# 7seg-micro.net
KiCad netlist of a schematic drawn in EAGLE
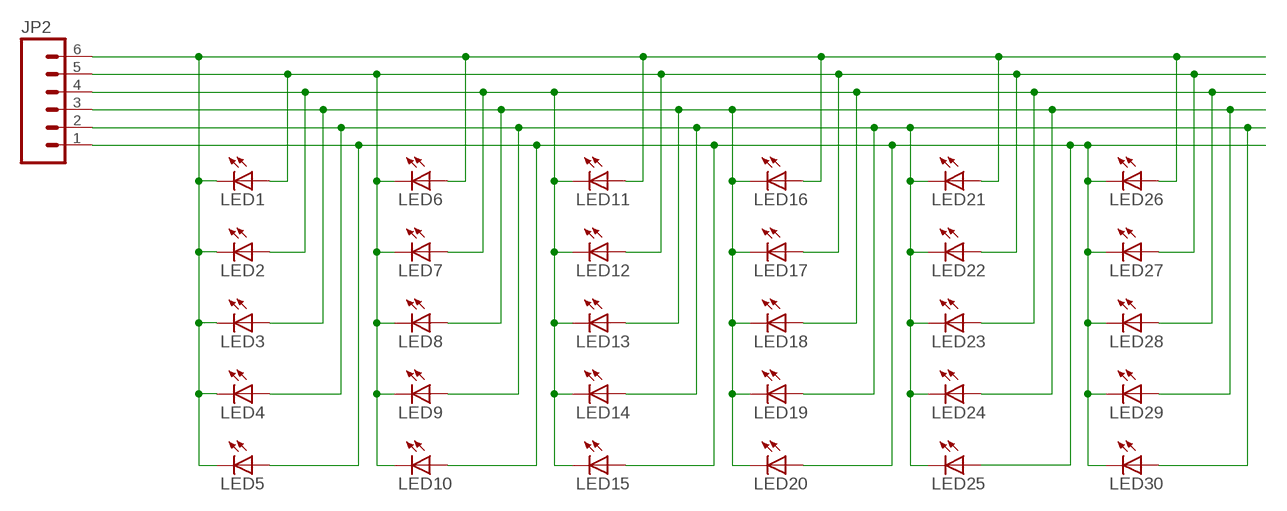
[diagram p0: schematic, sheet 1]

(export (version "E")
  (design (tool "Eeschema 10.0.6"))
  (components
    (comp (ref "JP2")
      (value "M06NO_SILK_FEMALE_PTH")
      (footprint "eagle-import:1X06_NO_SILK")
      (libsource (lib "eagle-import") (part "M06NO_SILK_FEMALE_PTH"))
    )
    (comp (ref "LED1")
      (value "LED0603")
      (footprint "eagle-import:LED-0603")
      (libsource (lib "eagle-import") (part "LED0603"))
    )
    (comp (ref "LED2")
      (value "LED0603")
      (footprint "eagle-import:LED-0603")
      (libsource (lib "eagle-import") (part "LED0603"))
    )
    (comp (ref "LED3")
      (value "LED0603")
      (footprint "eagle-import:LED-0603")
      (libsource (lib "eagle-import") (part "LED0603"))
    )
    (comp (ref "LED4")
      (value "LED0603")
      (footprint "eagle-import:LED-0603")
      (libsource (lib "eagle-import") (part "LED0603"))
    )
    (comp (ref "LED5")
      (value "LED0603")
      (footprint "eagle-import:LED-0603")
      (libsource (lib "eagle-import") (part "LED0603"))
    )
    (comp (ref "LED6")
      (value "LED0603")
      (footprint "eagle-import:LED-0603")
      (libsource (lib "eagle-import") (part "LED0603"))
    )
    (comp (ref "LED7")
      (value "LED0603")
      (footprint "eagle-import:LED-0603")
      (libsource (lib "eagle-import") (part "LED0603"))
    )
    (comp (ref "LED8")
      (value "LED0603")
      (footprint "eagle-import:LED-0603")
      (libsource (lib "eagle-import") (part "LED0603"))
    )
    (comp (ref "LED9")
      (value "LED0603")
      (footprint "eagle-import:LED-0603")
      (libsource (lib "eagle-import") (part "LED0603"))
    )
    (comp (ref "LED10")
      (value "LED0603")
      (footprint "eagle-import:LED-0603")
      (libsource (lib "eagle-import") (part "LED0603"))
    )
    (comp (ref "LED11")
      (value "LED0603")
      (footprint "eagle-import:LED-0603")
      (libsource (lib "eagle-import") (part "LED0603"))
    )
    (comp (ref "LED12")
      (value "LED0603")
      (footprint "eagle-import:LED-0603")
      (libsource (lib "eagle-import") (part "LED0603"))
    )
    (comp (ref "LED13")
      (value "LED0603")
      (footprint "eagle-import:LED-0603")
      (libsource (lib "eagle-import") (part "LED0603"))
    )
    (comp (ref "LED14")
      (value "LED0603")
      (footprint "eagle-import:LED-0603")
      (libsource (lib "eagle-import") (part "LED0603"))
    )
    (comp (ref "LED15")
      (value "LED0603")
      (footprint "eagle-import:LED-0603")
      (libsource (lib "eagle-import") (part "LED0603"))
    )
    (comp (ref "LED16")
      (value "LED0603")
      (footprint "eagle-import:LED-0603")
      (libsource (lib "eagle-import") (part "LED0603"))
    )
    (comp (ref "LED17")
      (value "LED0603")
      (footprint "eagle-import:LED-0603")
      (libsource (lib "eagle-import") (part "LED0603"))
    )
    (comp (ref "LED18")
      (value "LED0603")
      (footprint "eagle-import:LED-0603")
      (libsource (lib "eagle-import") (part "LED0603"))
    )
    (comp (ref "LED19")
      (value "LED0603")
      (footprint "eagle-import:LED-0603")
      (libsource (lib "eagle-import") (part "LED0603"))
    )
    (comp (ref "LED20")
      (value "LED0603")
      (footprint "eagle-import:LED-0603")
      (libsource (lib "eagle-import") (part "LED0603"))
    )
    (comp (ref "LED21")
      (value "LED0603")
      (footprint "eagle-import:LED-0603")
      (libsource (lib "eagle-import") (part "LED0603"))
    )
    (comp (ref "LED22")
      (value "LED0603")
      (footprint "eagle-import:LED-0603")
      (libsource (lib "eagle-import") (part "LED0603"))
    )
    (comp (ref "LED23")
      (value "LED0603")
      (footprint "eagle-import:LED-0603")
      (libsource (lib "eagle-import") (part "LED0603"))
    )
    (comp (ref "LED24")
      (value "LED0603")
      (footprint "eagle-import:LED-0603")
      (libsource (lib "eagle-import") (part "LED0603"))
    )
    (comp (ref "LED25")
      (value "LED0603")
      (footprint "eagle-import:LED-0603")
      (libsource (lib "eagle-import") (part "LED0603"))
    )
    (comp (ref "LED26")
      (value "LED0603")
      (footprint "eagle-import:LED-0603")
      (libsource (lib "eagle-import") (part "LED0603"))
    )
    (comp (ref "LED27")
      (value "LED0603")
      (footprint "eagle-import:LED-0603")
      (libsource (lib "eagle-import") (part "LED0603"))
    )
    (comp (ref "LED28")
      (value "LED0603")
      (footprint "eagle-import:LED-0603")
      (libsource (lib "eagle-import") (part "LED0603"))
    )
    (comp (ref "LED29")
      (value "LED0603")
      (footprint "eagle-import:LED-0603")
      (libsource (lib "eagle-import") (part "LED0603"))
    )
    (comp (ref "LED30")
      (value "LED0603")
      (footprint "eagle-import:LED-0603")
      (libsource (lib "eagle-import") (part "LED0603"))
    )
  )
  (nets
    (net (code "1") (name "Net-(JP2-Pad1)") (class "Default")
      (node (ref "JP2") (pin "1") (pinfunction "1_1") (pintype "passive"))
      (node (ref "LED10") (pin "A") (pinfunction "A_A") (pintype "passive"))
      (node (ref "LED15") (pin "A") (pinfunction "A_A") (pintype "passive"))
      (node (ref "LED20") (pin "A") (pinfunction "A_A") (pintype "passive"))
      (node (ref "LED25") (pin "A") (pinfunction "A_A") (pintype "passive"))
      (node (ref "LED26") (pin "C") (pinfunction "C_C") (pintype "passive"))
      (node (ref "LED27") (pin "C") (pinfunction "C_C") (pintype "passive"))
      (node (ref "LED28") (pin "C") (pinfunction "C_C") (pintype "passive"))
      (node (ref "LED29") (pin "C") (pinfunction "C_C") (pintype "passive"))
      (node (ref "LED30") (pin "C") (pinfunction "C_C") (pintype "passive"))
      (node (ref "LED5") (pin "A") (pinfunction "A_A") (pintype "passive"))
    )
    (net (code "2") (name "Net-(JP2-Pad2)") (class "Default")
      (node (ref "JP2") (pin "2") (pinfunction "2_2") (pintype "passive"))
      (node (ref "LED14") (pin "A") (pinfunction "A_A") (pintype "passive"))
      (node (ref "LED19") (pin "A") (pinfunction "A_A") (pintype "passive"))
      (node (ref "LED21") (pin "C") (pinfunction "C_C") (pintype "passive"))
      (node (ref "LED22") (pin "C") (pinfunction "C_C") (pintype "passive"))
      (node (ref "LED23") (pin "C") (pinfunction "C_C") (pintype "passive"))
      (node (ref "LED24") (pin "C") (pinfunction "C_C") (pintype "passive"))
      (node (ref "LED25") (pin "C") (pinfunction "C_C") (pintype "passive"))
      (node (ref "LED30") (pin "A") (pinfunction "A_A") (pintype "passive"))
      (node (ref "LED4") (pin "A") (pinfunction "A_A") (pintype "passive"))
      (node (ref "LED9") (pin "A") (pinfunction "A_A") (pintype "passive"))
    )
    (net (code "3") (name "Net-(JP2-Pad3)") (class "Default")
      (node (ref "JP2") (pin "3") (pinfunction "3_3") (pintype "passive"))
      (node (ref "LED13") (pin "A") (pinfunction "A_A") (pintype "passive"))
      (node (ref "LED16") (pin "C") (pinfunction "C_C") (pintype "passive"))
      (node (ref "LED17") (pin "C") (pinfunction "C_C") (pintype "passive"))
      (node (ref "LED18") (pin "C") (pinfunction "C_C") (pintype "passive"))
      (node (ref "LED19") (pin "C") (pinfunction "C_C") (pintype "passive"))
      (node (ref "LED20") (pin "C") (pinfunction "C_C") (pintype "passive"))
      (node (ref "LED24") (pin "A") (pinfunction "A_A") (pintype "passive"))
      (node (ref "LED29") (pin "A") (pinfunction "A_A") (pintype "passive"))
      (node (ref "LED3") (pin "A") (pinfunction "A_A") (pintype "passive"))
      (node (ref "LED8") (pin "A") (pinfunction "A_A") (pintype "passive"))
    )
    (net (code "4") (name "Net-(JP2-Pad4)") (class "Default")
      (node (ref "JP2") (pin "4") (pinfunction "4_4") (pintype "passive"))
      (node (ref "LED11") (pin "C") (pinfunction "C_C") (pintype "passive"))
      (node (ref "LED12") (pin "C") (pinfunction "C_C") (pintype "passive"))
      (node (ref "LED13") (pin "C") (pinfunction "C_C") (pintype "passive"))
      (node (ref "LED14") (pin "C") (pinfunction "C_C") (pintype "passive"))
      (node (ref "LED15") (pin "C") (pinfunction "C_C") (pintype "passive"))
      (node (ref "LED18") (pin "A") (pinfunction "A_A") (pintype "passive"))
      (node (ref "LED2") (pin "A") (pinfunction "A_A") (pintype "passive"))
      (node (ref "LED23") (pin "A") (pinfunction "A_A") (pintype "passive"))
      (node (ref "LED28") (pin "A") (pinfunction "A_A") (pintype "passive"))
      (node (ref "LED7") (pin "A") (pinfunction "A_A") (pintype "passive"))
    )
    (net (code "5") (name "Net-(JP2-Pad5)") (class "Default")
      (node (ref "JP2") (pin "5") (pinfunction "5_5") (pintype "passive"))
      (node (ref "LED1") (pin "A") (pinfunction "A_A") (pintype "passive"))
      (node (ref "LED10") (pin "C") (pinfunction "C_C") (pintype "passive"))
      (node (ref "LED12") (pin "A") (pinfunction "A_A") (pintype "passive"))
      (node (ref "LED17") (pin "A") (pinfunction "A_A") (pintype "passive"))
      (node (ref "LED22") (pin "A") (pinfunction "A_A") (pintype "passive"))
      (node (ref "LED27") (pin "A") (pinfunction "A_A") (pintype "passive"))
      (node (ref "LED6") (pin "C") (pinfunction "C_C") (pintype "passive"))
      (node (ref "LED7") (pin "C") (pinfunction "C_C") (pintype "passive"))
      (node (ref "LED8") (pin "C") (pinfunction "C_C") (pintype "passive"))
      (node (ref "LED9") (pin "C") (pinfunction "C_C") (pintype "passive"))
    )
    (net (code "6") (name "Net-(JP2-Pad6)") (class "Default")
      (node (ref "JP2") (pin "6") (pinfunction "6_6") (pintype "passive"))
      (node (ref "LED1") (pin "C") (pinfunction "C_C") (pintype "passive"))
      (node (ref "LED11") (pin "A") (pinfunction "A_A") (pintype "passive"))
      (node (ref "LED16") (pin "A") (pinfunction "A_A") (pintype "passive"))
      (node (ref "LED2") (pin "C") (pinfunction "C_C") (pintype "passive"))
      (node (ref "LED21") (pin "A") (pinfunction "A_A") (pintype "passive"))
      (node (ref "LED26") (pin "A") (pinfunction "A_A") (pintype "passive"))
      (node (ref "LED3") (pin "C") (pinfunction "C_C") (pintype "passive"))
      (node (ref "LED4") (pin "C") (pinfunction "C_C") (pintype "passive"))
      (node (ref "LED5") (pin "C") (pinfunction "C_C") (pintype "passive"))
      (node (ref "LED6") (pin "A") (pinfunction "A_A") (pintype "passive"))
    )
  )
)
